# NB992F_POWER_V17.net
KiCad netlist of a schematic drawn in Altium Designer
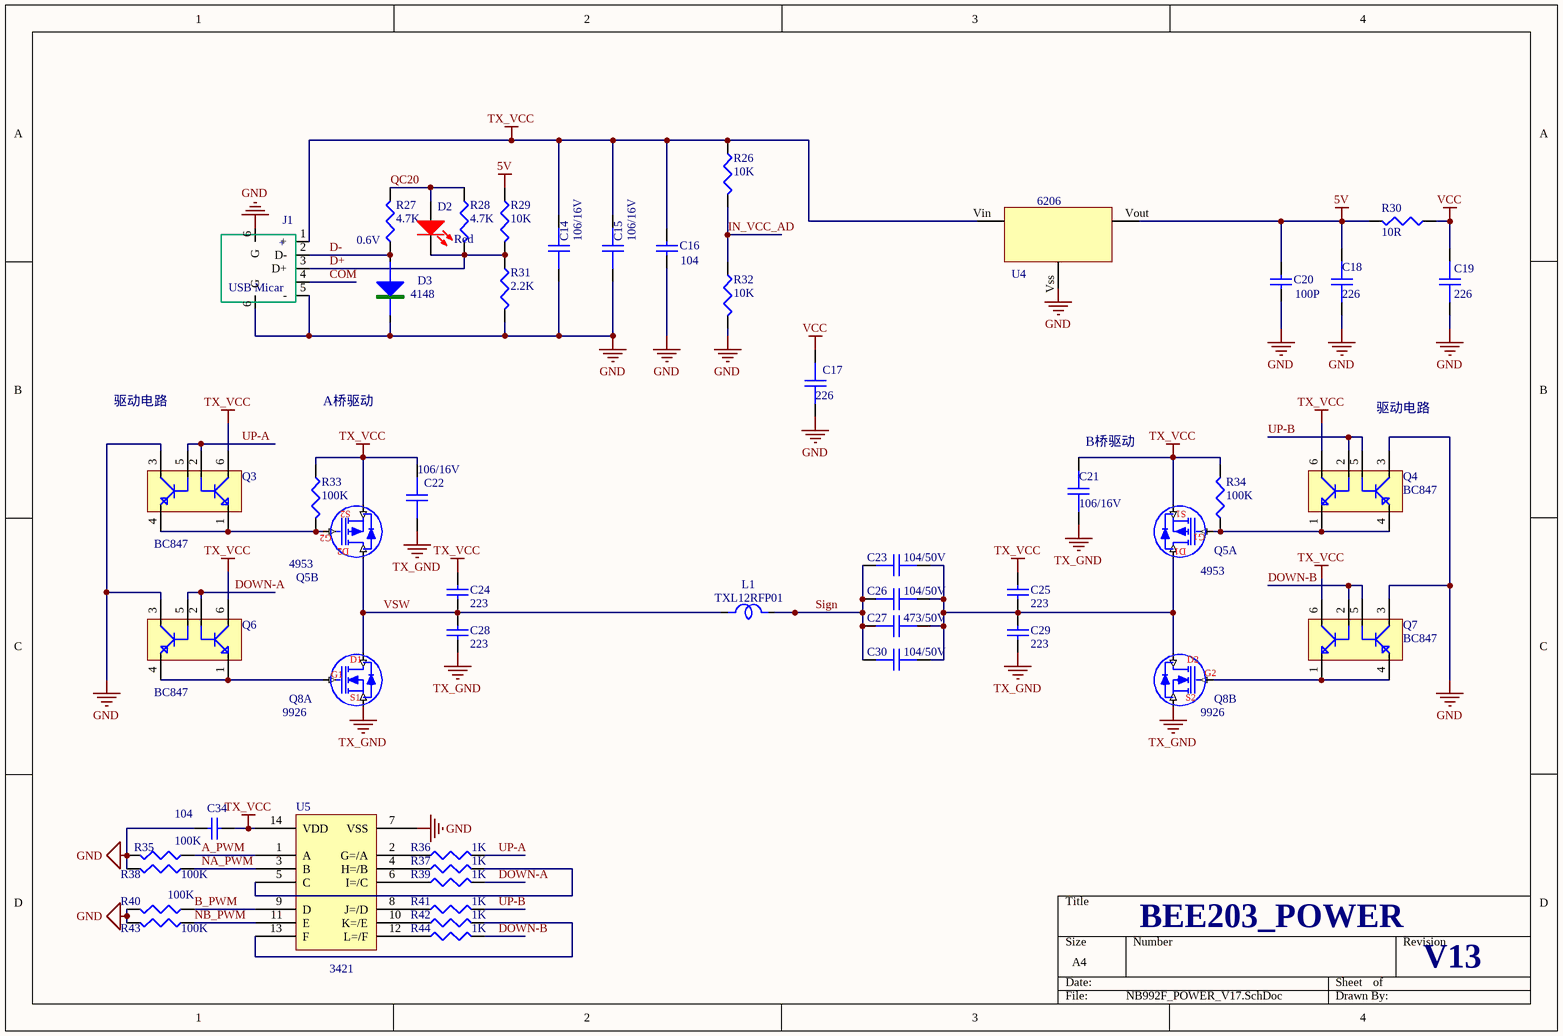
[diagram p0: NB992F_POWER_V17.SchDoc]

(export (version "E")
  (design (tool "Eeschema 10.0.6"))
  (components
    (comp (ref "C14") (value "106/16V") (footprint "C0805") (libsource (lib "*") (part "CH")))
    (comp (ref "C15") (value "106/16V") (footprint "C0805") (libsource (lib "*") (part "CH")))
    (comp (ref "C16")
      (value "104")
      (footprint "C0402")
      (description "Capacitor")
      (fields (field (name "PUBLISHER") "Altium Limited"))
      (libsource (lib "*") (part "Cap"))
    )
    (comp (ref "C17") (value "226") (footprint "C0603") (libsource (lib "*") (part "CH")))
    (comp (ref "C18") (value "226") (footprint "C0805") (libsource (lib "*") (part "CH")))
    (comp (ref "C19") (value "226") (footprint "C0805") (libsource (lib "*") (part "CH")))
    (comp (ref "C20")
      (value "100P")
      (footprint "C0402")
      (description "Capacitor")
      (fields (field (name "PUBLISHER") "Altium Limited"))
      (libsource (lib "*") (part "Cap"))
    )
    (comp (ref "C21") (value "106/16V") (footprint "C0805") (libsource (lib "*") (part "CH")))
    (comp (ref "C22") (value "106/16V") (footprint "C0805") (libsource (lib "*") (part "CH")))
    (comp (ref "C23") (value "104/50V") (footprint "C1206") (libsource (lib "*") (part "CH")))
    (comp (ref "C24")
      (value "223")
      (footprint "C0603")
      (description "Capacitor")
      (fields (field (name "PUBLISHER") "Altium Limited"))
      (libsource (lib "*") (part "Cap"))
    )
    (comp (ref "C25")
      (value "223")
      (footprint "C0603")
      (description "Capacitor")
      (fields (field (name "PUBLISHER") "Altium Limited"))
      (libsource (lib "*") (part "Cap"))
    )
    (comp (ref "C26") (value "104/50V") (footprint "C1206") (libsource (lib "*") (part "CH")))
    (comp (ref "C27") (value "473/50V") (footprint "C1206") (libsource (lib "*") (part "CH")))
    (comp (ref "C28")
      (value "223")
      (footprint "C0603")
      (description "Capacitor")
      (fields (field (name "PUBLISHER") "Altium Limited"))
      (libsource (lib "*") (part "Cap"))
    )
    (comp (ref "C29")
      (value "223")
      (footprint "C0603")
      (description "Capacitor")
      (fields (field (name "PUBLISHER") "Altium Limited"))
      (libsource (lib "*") (part "Cap"))
    )
    (comp (ref "C30") (value "104/50V") (footprint "C1206") (libsource (lib "*") (part "CH")))
    (comp (ref "C34")
      (value "104")
      (footprint "C0402")
      (description "Capacitor")
      (fields (field (name "PUBLISHER") "Altium Limited"))
      (libsource (lib "*") (part "Cap"))
    )
    (comp (ref "D2") (value "Red") (footprint "LED0603") (libsource (lib "XiaoQiang") (part "LED02")))
    (comp (ref "D3")
      (value "4148")
      (footprint "SOD323")
      (description "1N4001")
      (libsource (lib "*") (part "D0"))
    )
    (comp (ref "J1") (value "USB Micar") (footprint "USB MRO") (libsource (lib "LXZ SCH LIB") (part "USB")))
    (comp (ref "L1")
      (value "TXL12RFP01")
      (footprint "SPIN2_5mm")
      (description "1uH")
      (libsource (lib "*") (part "L"))
    )
    (comp (ref "Q3") (value "BC847") (footprint "SOT-363") (libsource (lib "") (part "D_PNP_1")))
    (comp (ref "Q4") (value "BC847") (footprint "SOT-363") (libsource (lib "IC_DimoV50") (part "D_PNP")))
    (comp (ref "Q5") (value "4953") (footprint "SOP8D") (libsource (lib "lxzschlib") (part "MOSFETP2")))
    (comp (ref "Q6") (value "BC847") (footprint "SOT-363") (libsource (lib "") (part "D_PNP_1")))
    (comp (ref "Q7") (value "BC847") (footprint "SOT-363") (libsource (lib "IC_DimoV50") (part "D_PNP")))
    (comp (ref "Q8") (value "9926") (footprint "SOP8D") (libsource (lib "lxzschlib") (part "MOSFETN2")))
    (comp (ref "R26") (value "10K") (footprint "R0402") (description "1K") (libsource (lib "*") (part "R")))
    (comp (ref "R27") (value "4.7K") (footprint "R0402") (description "1K") (libsource (lib "*") (part "R")))
    (comp (ref "R28") (value "4.7K") (footprint "R0402") (description "1K") (libsource (lib "*") (part "R")))
    (comp (ref "R29") (value "10K") (footprint "R0402") (description "1K") (libsource (lib "*") (part "R")))
    (comp (ref "R30") (value "10R") (footprint "R0402") (description "1K") (libsource (lib "*") (part "R")))
    (comp (ref "R31") (value "2.2K") (footprint "R0402") (description "1K") (libsource (lib "*") (part "R")))
    (comp (ref "R32") (value "10K") (footprint "R0402") (description "1K") (libsource (lib "*") (part "R")))
    (comp (ref "R33") (value "100K") (footprint "R0402") (description "1K") (libsource (lib "*") (part "R")))
    (comp (ref "R34") (value "100K") (footprint "R0402") (description "1K") (libsource (lib "*") (part "R")))
    (comp (ref "R35") (value "100K") (footprint "R0402") (description "1K") (libsource (lib "*") (part "R")))
    (comp (ref "R36") (value "1K") (footprint "R0402") (libsource (lib "*") (part "R")))
    (comp (ref "R37") (value "1K") (footprint "R0402") (libsource (lib "*") (part "R")))
    (comp (ref "R38") (value "100K") (footprint "R0402") (description "1K") (libsource (lib "*") (part "R")))
    (comp (ref "R39") (value "1K") (footprint "R0402") (libsource (lib "*") (part "R")))
    (comp (ref "R40") (value "100K") (footprint "R0402") (description "1K") (libsource (lib "*") (part "R")))
    (comp (ref "R41") (value "1K") (footprint "R0402") (libsource (lib "*") (part "R")))
    (comp (ref "R42") (value "1K") (footprint "R0402") (libsource (lib "*") (part "R")))
    (comp (ref "R43") (value "100K") (footprint "R0402") (description "1K") (libsource (lib "*") (part "R")))
    (comp (ref "R44") (value "1K") (footprint "R0402") (libsource (lib "*") (part "R")))
    (comp (ref "U4") (value "6206") (footprint "SOT-89-5V") (libsource (lib "*") (part "VOLTREG")))
    (comp (ref "U5") (value "3421") (footprint "SOP14") (libsource (lib "Schlib1") (part "CD4069")))
  )
  (nets
    (net (code "1") (name "/A_PWM") (class "Default")
      (node (ref "R35") (pin "1") (pintype "passive"))
      (node (ref "U5") (pin "1") (pinfunction "A_1") (pintype "passive"))
    )
    (net (code "2") (name "/B_PWM") (class "Default")
      (node (ref "R40") (pin "1") (pintype "passive"))
      (node (ref "U5") (pin "9") (pinfunction "D_9") (pintype "passive"))
    )
    (net (code "3") (name "/COM") (class "Default") (node (ref "J1") (pin "4") (pintype "passive")))
    (net (code "4") (name "/D+") (class "Default")
      (node (ref "D2") (pin "2") (pinfunction "K_2") (pintype "passive"))
      (node (ref "J1") (pin "3") (pinfunction "D+_3") (pintype "passive"))
      (node (ref "R28") (pin "1") (pintype "passive"))
      (node (ref "R29") (pin "1") (pintype "passive"))
      (node (ref "R31") (pin "2") (pintype "passive"))
    )
    (net (code "5") (name "/D-") (class "Default")
      (node (ref "D3") (pin "1") (pintype "passive"))
      (node (ref "J1") (pin "2") (pinfunction "D-_2") (pintype "passive"))
      (node (ref "R27") (pin "2") (pintype "passive"))
    )
    (net (code "6") (name "/DOWN-A") (class "Default")
      (node (ref "Q6") (pin "2") (pinfunction "2_2") (pintype "passive"))
      (node (ref "Q6") (pin "5") (pinfunction "5_5") (pintype "passive"))
      (node (ref "R39") (pin "2") (pintype "passive"))
    )
    (net (code "7") (name "/DOWN-B") (class "Default")
      (node (ref "Q7") (pin "2") (pinfunction "2_2") (pintype "passive"))
      (node (ref "Q7") (pin "5") (pinfunction "5_5") (pintype "passive"))
      (node (ref "R44") (pin "2") (pintype "passive"))
    )
    (net (code "8") (name "/IN_VCC_AD") (class "Default")
      (node (ref "R26") (pin "1") (pintype "passive"))
      (node (ref "R32") (pin "2") (pintype "passive"))
    )
    (net (code "9") (name "/NA_PWM") (class "Default")
      (node (ref "R38") (pin "1") (pintype "passive"))
      (node (ref "U5") (pin "3") (pinfunction "B_3") (pintype "passive"))
    )
    (net (code "10") (name "/NB_PWM") (class "Default")
      (node (ref "R43") (pin "1") (pintype "passive"))
      (node (ref "U5") (pin "11") (pinfunction "E_11") (pintype "passive"))
    )
    (net (code "11") (name "/QC20") (class "Default")
      (node (ref "D2") (pin "1") (pinfunction "A_1") (pintype "passive"))
      (node (ref "R27") (pin "1") (pintype "passive"))
      (node (ref "R28") (pin "2") (pintype "passive"))
    )
    (net (code "12") (name "/Sign") (class "Default")
      (node (ref "C23") (pin "1") (pintype "passive"))
      (node (ref "C26") (pin "1") (pintype "passive"))
      (node (ref "C27") (pin "1") (pintype "passive"))
      (node (ref "C30") (pin "1") (pintype "passive"))
      (node (ref "L1") (pin "2") (pintype "passive"))
    )
    (net (code "13") (name "/UP-A") (class "Default")
      (node (ref "Q3") (pin "2") (pinfunction "2_2") (pintype "passive"))
      (node (ref "Q3") (pin "5") (pinfunction "5_5") (pintype "passive"))
      (node (ref "R36") (pin "2") (pintype "passive"))
    )
    (net (code "14") (name "/UP-B") (class "Default")
      (node (ref "Q4") (pin "2") (pinfunction "2_2") (pintype "passive"))
      (node (ref "Q4") (pin "5") (pinfunction "5_5") (pintype "passive"))
      (node (ref "R41") (pin "2") (pintype "passive"))
    )
    (net (code "15") (name "/VSW") (class "Default")
      (node (ref "C24") (pin "1") (pinfunction "1_1") (pintype "passive"))
      (node (ref "C28") (pin "2") (pinfunction "2_2") (pintype "passive"))
      (node (ref "L1") (pin "1") (pintype "passive"))
      (node (ref "Q5") (pin "C2") (pinfunction "D2_C2") (pintype "input"))
      (node (ref "Q8") (pin "C1") (pinfunction "D1_C1") (pintype "input"))
    )
    (net (code "16") (name "5V") (class "Default")
      (node (ref "C18") (pin "1") (pintype "passive"))
      (node (ref "C20") (pin "1") (pinfunction "1_1") (pintype "passive"))
      (node (ref "R29") (pin "2") (pintype "passive"))
      (node (ref "R30") (pin "2") (pintype "passive"))
      (node (ref "U4") (pin "Vout") (pintype "passive"))
    )
    (net (code "17") (name "GND") (class "Default")
      (node (ref "C14") (pin "2") (pintype "passive"))
      (node (ref "C15") (pin "2") (pintype "passive"))
      (node (ref "C16") (pin "2") (pinfunction "2_2") (pintype "passive"))
      (node (ref "C17") (pin "1") (pintype "passive"))
      (node (ref "C18") (pin "2") (pintype "passive"))
      (node (ref "C19") (pin "1") (pintype "passive"))
      (node (ref "C20") (pin "2") (pinfunction "2_2") (pintype "passive"))
      (node (ref "C34") (pin "1") (pinfunction "1_1") (pintype "passive"))
      (node (ref "D3") (pin "2") (pintype "passive"))
      (node (ref "J1") (pin "5") (pinfunction "-_5") (pintype "passive"))
      (node (ref "J1") (pin "6") (pinfunction "G_6") (pintype "passive"))
      (node (ref "Q3") (pin "3") (pinfunction "3_3") (pintype "passive"))
      (node (ref "Q4") (pin "3") (pinfunction "3_3") (pintype "passive"))
      (node (ref "Q6") (pin "3") (pinfunction "3_3") (pintype "passive"))
      (node (ref "Q7") (pin "3") (pinfunction "3_3") (pintype "passive"))
      (node (ref "R31") (pin "1") (pintype "passive"))
      (node (ref "R32") (pin "1") (pintype "passive"))
      (node (ref "R35") (pin "2") (pintype "passive"))
      (node (ref "R38") (pin "2") (pintype "passive"))
      (node (ref "R40") (pin "2") (pintype "passive"))
      (node (ref "R43") (pin "2") (pintype "passive"))
      (node (ref "U4") (pin "Vss") (pintype "passive"))
      (node (ref "U5") (pin "7") (pinfunction "VSS_7") (pintype "passive"))
    )
    (net (code "18") (name "Net-(Q5A-D1)") (class "Default")
      (node (ref "C23") (pin "2") (pintype "passive"))
      (node (ref "C25") (pin "1") (pinfunction "1_1") (pintype "passive"))
      (node (ref "C26") (pin "2") (pintype "passive"))
      (node (ref "C27") (pin "2") (pintype "passive"))
      (node (ref "C29") (pin "2") (pinfunction "2_2") (pintype "passive"))
      (node (ref "C30") (pin "2") (pintype "passive"))
      (node (ref "Q5") (pin "C1") (pinfunction "D1_C1") (pintype "input"))
      (node (ref "Q8") (pin "C2") (pinfunction "D2_C2") (pintype "input"))
    )
    (net (code "19") (name "Net-(Q5A-G1)") (class "Default")
      (node (ref "Q4") (pin "1") (pinfunction "1_1") (pintype "passive"))
      (node (ref "Q4") (pin "4") (pinfunction "4_4") (pintype "passive"))
      (node (ref "Q5") (pin "B1") (pinfunction "G1_B1") (pintype "input"))
      (node (ref "R34") (pin "1") (pintype "passive"))
    )
    (net (code "20") (name "Net-(Q5B-G2)") (class "Default")
      (node (ref "Q3") (pin "1") (pinfunction "1_1") (pintype "passive"))
      (node (ref "Q3") (pin "4") (pinfunction "4_4") (pintype "passive"))
      (node (ref "Q5") (pin "B2") (pinfunction "G2_B2") (pintype "input"))
      (node (ref "R33") (pin "2") (pintype "passive"))
    )
    (net (code "21") (name "Net-(Q8A-G1)") (class "Default")
      (node (ref "Q6") (pin "1") (pinfunction "1_1") (pintype "passive"))
      (node (ref "Q6") (pin "4") (pinfunction "4_4") (pintype "passive"))
      (node (ref "Q8") (pin "B1") (pinfunction "G1_B1") (pintype "input"))
    )
    (net (code "22") (name "Net-(Q8B-G2)") (class "Default")
      (node (ref "Q7") (pin "1") (pinfunction "1_1") (pintype "passive"))
      (node (ref "Q7") (pin "4") (pinfunction "4_4") (pintype "passive"))
      (node (ref "Q8") (pin "B2") (pinfunction "G2_B2") (pintype "input"))
    )
    (net (code "23") (name "Net-(U5-C)") (class "Default")
      (node (ref "R37") (pin "2") (pintype "passive"))
      (node (ref "U5") (pin "5") (pinfunction "C_5") (pintype "passive"))
    )
    (net (code "24") (name "Net-(U5-F)") (class "Default")
      (node (ref "R42") (pin "2") (pintype "passive"))
      (node (ref "U5") (pin "13") (pinfunction "F_13") (pintype "passive"))
    )
    (net (code "25") (name "Net-(U5-G={slash}A)") (class "Default")
      (node (ref "R36") (pin "1") (pintype "passive"))
      (node (ref "U5") (pin "2") (pinfunction "G=/A_2") (pintype "passive"))
    )
    (net (code "26") (name "Net-(U5-H={slash}B)") (class "Default")
      (node (ref "R37") (pin "1") (pintype "passive"))
      (node (ref "U5") (pin "4") (pinfunction "H=/B_4") (pintype "passive"))
    )
    (net (code "27") (name "Net-(U5-I={slash}C)") (class "Default")
      (node (ref "R39") (pin "1") (pintype "passive"))
      (node (ref "U5") (pin "6") (pinfunction "I=/C_6") (pintype "passive"))
    )
    (net (code "28") (name "Net-(U5-J={slash}D)") (class "Default")
      (node (ref "R41") (pin "1") (pintype "passive"))
      (node (ref "U5") (pin "8") (pinfunction "J=/D_8") (pintype "passive"))
    )
    (net (code "29") (name "Net-(U5-K={slash}E)") (class "Default")
      (node (ref "R42") (pin "1") (pintype "passive"))
      (node (ref "U5") (pin "10") (pinfunction "K=/E_10") (pintype "passive"))
    )
    (net (code "30") (name "Net-(U5-L={slash}F)") (class "Default")
      (node (ref "R44") (pin "1") (pintype "passive"))
      (node (ref "U5") (pin "12") (pinfunction "L=/F_12") (pintype "passive"))
    )
    (net (code "31") (name "TX_GND") (class "Default")
      (node (ref "C21") (pin "2") (pintype "passive"))
      (node (ref "C22") (pin "2") (pintype "passive"))
      (node (ref "C28") (pin "1") (pinfunction "1_1") (pintype "passive"))
      (node (ref "C29") (pin "1") (pinfunction "1_1") (pintype "passive"))
      (node (ref "Q8") (pin "E1") (pinfunction "S1_E1") (pintype "input"))
      (node (ref "Q8") (pin "E2") (pinfunction "S2_E2") (pintype "input"))
    )
    (net (code "32") (name "TX_VCC") (class "Default")
      (node (ref "C14") (pin "1") (pintype "passive"))
      (node (ref "C15") (pin "1") (pintype "passive"))
      (node (ref "C16") (pin "1") (pinfunction "1_1") (pintype "passive"))
      (node (ref "C21") (pin "1") (pintype "passive"))
      (node (ref "C22") (pin "1") (pintype "passive"))
      (node (ref "C24") (pin "2") (pinfunction "2_2") (pintype "passive"))
      (node (ref "C25") (pin "2") (pinfunction "2_2") (pintype "passive"))
      (node (ref "C34") (pin "2") (pinfunction "2_2") (pintype "passive"))
      (node (ref "J1") (pin "1") (pinfunction "+_1") (pintype "passive"))
      (node (ref "Q3") (pin "6") (pinfunction "6_6") (pintype "passive"))
      (node (ref "Q4") (pin "6") (pinfunction "6_6") (pintype "passive"))
      (node (ref "Q5") (pin "E1") (pinfunction "S1_E1") (pintype "input"))
      (node (ref "Q5") (pin "E2") (pinfunction "S2_E2") (pintype "input"))
      (node (ref "Q6") (pin "6") (pinfunction "6_6") (pintype "passive"))
      (node (ref "Q7") (pin "6") (pinfunction "6_6") (pintype "passive"))
      (node (ref "R26") (pin "2") (pintype "passive"))
      (node (ref "R33") (pin "1") (pintype "passive"))
      (node (ref "R34") (pin "2") (pintype "passive"))
      (node (ref "U4") (pin "Vin") (pintype "passive"))
      (node (ref "U5") (pin "14") (pinfunction "VDD_14") (pintype "passive"))
    )
    (net (code "33") (name "VCC") (class "Default")
      (node (ref "C17") (pin "2") (pintype "passive"))
      (node (ref "C19") (pin "2") (pintype "passive"))
      (node (ref "R30") (pin "1") (pintype "passive"))
    )
  )
)
